# usb3.net
KiCad netlist of a schematic drawn in EAGLE
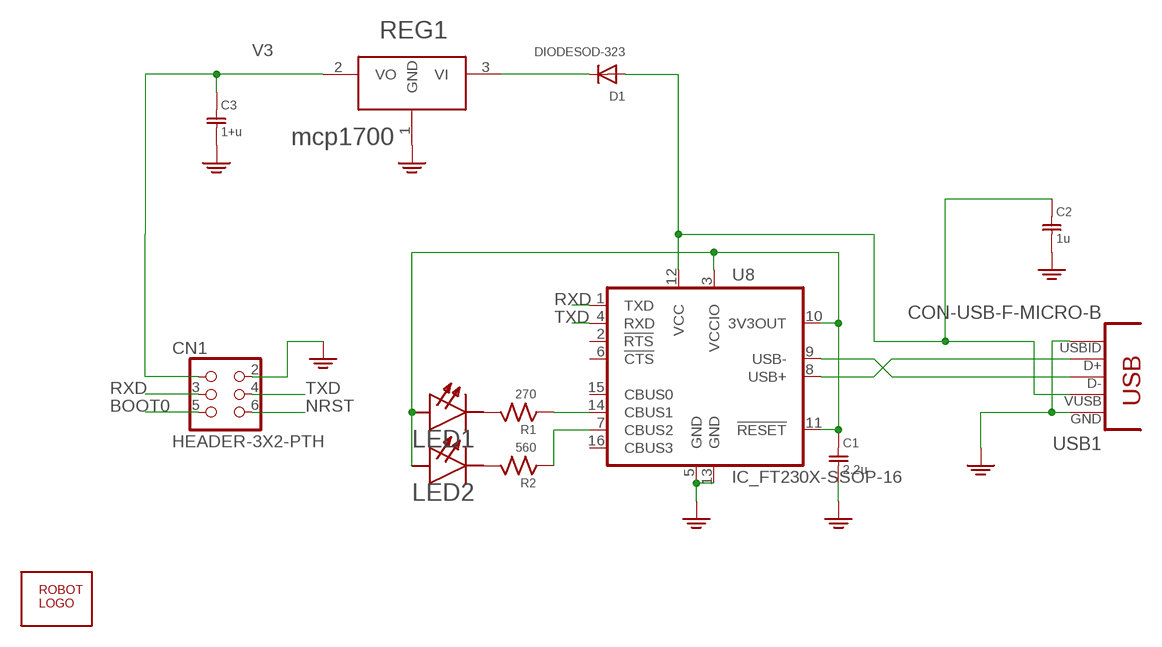
[diagram p0: schematic, sheet 1]

(export (version "E")
  (design (tool "Eeschema 10.0.6"))
  (components
    (comp (ref "C1")
      (value "2.2u")
      (footprint "eagle-import:SMD0603")
      (libsource (lib "eagle-import") (part "C0603"))
    )
    (comp (ref "C2")
      (value "1u")
      (footprint "eagle-import:SMD0603")
      (libsource (lib "eagle-import") (part "C0603"))
    )
    (comp (ref "C3")
      (value "1+u")
      (footprint "eagle-import:SMD0603")
      (libsource (lib "eagle-import") (part "C0603"))
    )
    (comp (ref "CN1")
      (value "HEADER-3X2-PTH")
      (footprint "eagle-import:HEADER-3X2-PTH")
      (libsource (lib "eagle-import") (part "HEADER-3X2-PTH"))
    )
    (comp (ref "D1")
      (value "DIODESOD-323")
      (footprint "eagle-import:SOD-323")
      (libsource (lib "eagle-import") (part "DIODESOD-323"))
    )
    (comp (ref "LED1")
      (value "GREEN")
      (footprint "eagle-import:SMD0603D")
      (libsource (lib "eagle-import") (part "LED"))
    )
    (comp (ref "LED2")
      (value "ORANGE")
      (footprint "eagle-import:SMD0603D")
      (libsource (lib "eagle-import") (part "LED"))
    )
    (comp (ref "R1")
      (value "270")
      (footprint "eagle-import:SMD0603")
      (libsource (lib "eagle-import") (part "R0603"))
    )
    (comp (ref "R2")
      (value "560")
      (footprint "eagle-import:SMD0603")
      (libsource (lib "eagle-import") (part "R0603"))
    )
    (comp (ref "REG1")
      (value "mcp1700")
      (footprint "eagle-import:SOT-23-3")
      (libsource (lib "eagle-import") (part "REGULATOR-SOT23-3"))
    )
    (comp (ref "U$1")
      (value "ROBOTMAN-LOGO")
      (footprint "eagle-import:ROBOTMAN-LOGO")
      (libsource (lib "eagle-import") (part "ROBOTMAN-LOGO"))
    )
    (comp (ref "U8")
      (value "IC_FT230X-SSOP-16")
      (footprint "eagle-import:SSOP-16-FTDI")
      (libsource (lib "eagle-import") (part "IC_FT230X-SSOP-16"))
    )
    (comp (ref "USB1")
      (value "CON-USB-F-MICRO-B")
      (footprint "eagle-import:CONN_USB_MICRO-B")
      (libsource (lib "eagle-import") (part "CON-USB-F-MICRO-B"))
    )
  )
  (nets
    (net (code "1") (name "/BOOT0") (class "Default")
      (node (ref "CN1") (pin "5") (pinfunction "P$5_5") (pintype "passive"))
    )
    (net (code "2") (name "/NRST") (class "Default")
      (node (ref "CN1") (pin "6") (pinfunction "P$6_6") (pintype "passive"))
    )
    (net (code "3") (name "/RXD") (class "Default")
      (node (ref "CN1") (pin "3") (pinfunction "P$3_3") (pintype "passive"))
      (node (ref "U8") (pin "1") (pinfunction "TXD_1") (pintype "output"))
    )
    (net (code "4") (name "/TXD") (class "Default")
      (node (ref "CN1") (pin "4") (pinfunction "P$4_4") (pintype "passive"))
      (node (ref "U8") (pin "4") (pinfunction "RXD_4") (pintype "input"))
    )
    (net (code "5") (name "/V3") (class "Default")
      (node (ref "C3") (pin "1") (pinfunction "P$1_1") (pintype "passive"))
      (node (ref "CN1") (pin "1") (pinfunction "P$1_1") (pintype "passive"))
      (node (ref "REG1") (pin "2") (pinfunction "VO_2") (pintype "bidirectional"))
    )
    (net (code "6") (name "Net-(C1-P$1)") (class "Default")
      (node (ref "C1") (pin "1") (pinfunction "P$1_1") (pintype "passive"))
      (node (ref "LED1") (pin "A") (pinfunction "A_A") (pintype "passive"))
      (node (ref "LED2") (pin "A") (pinfunction "A_A") (pintype "passive"))
      (node (ref "U8") (pin "10") (pinfunction "3V3OUT_10") (pintype "power_in"))
      (node (ref "U8") (pin "11") (pinfunction "~{RESET}_11") (pintype "bidirectional"))
      (node (ref "U8") (pin "3") (pinfunction "VCCIO_3") (pintype "power_in"))
    )
    (net (code "7") (name "Net-(C2-P$1)") (class "Default")
      (node (ref "C2") (pin "1") (pinfunction "P$1_1") (pintype "passive"))
      (node (ref "D1") (pin "A") (pinfunction "A_A") (pintype "passive"))
      (node (ref "U8") (pin "12") (pinfunction "VCC_12") (pintype "power_in"))
      (node (ref "USB1") (pin "P1") (pinfunction "VUSB_P1") (pintype "bidirectional"))
    )
    (net (code "8") (name "Net-(R1-P$1)") (class "Default")
      (node (ref "R1") (pin "1") (pinfunction "P$1_1") (pintype "passive"))
      (node (ref "U8") (pin "14") (pinfunction "CBUS1_14") (pintype "bidirectional"))
    )
    (net (code "9") (name "Net-(R1-P$2)") (class "Default")
      (node (ref "LED1") (pin "C") (pinfunction "C_C") (pintype "passive"))
      (node (ref "R1") (pin "2") (pinfunction "P$2_2") (pintype "passive"))
    )
    (net (code "10") (name "Net-(R2-P$1)") (class "Default")
      (node (ref "R2") (pin "1") (pinfunction "P$1_1") (pintype "passive"))
      (node (ref "U8") (pin "7") (pinfunction "CBUS2_7") (pintype "bidirectional"))
    )
    (net (code "11") (name "Net-(R2-P$2)") (class "Default")
      (node (ref "LED2") (pin "C") (pinfunction "C_C") (pintype "passive"))
      (node (ref "R2") (pin "2") (pinfunction "P$2_2") (pintype "passive"))
    )
    (net (code "12") (name "Net-(REG1-VI)") (class "Default")
      (node (ref "D1") (pin "C") (pinfunction "C_C") (pintype "passive"))
      (node (ref "REG1") (pin "3") (pinfunction "VI_3") (pintype "bidirectional"))
    )
    (net (code "13") (name "Net-(U8-USB+)") (class "Default")
      (node (ref "U8") (pin "8") (pinfunction "USB+_8") (pintype "output"))
      (node (ref "USB1") (pin "P3") (pinfunction "D+_P3") (pintype "bidirectional"))
    )
    (net (code "14") (name "Net-(U8-USB-)") (class "Default")
      (node (ref "U8") (pin "9") (pinfunction "USB-_9") (pintype "input"))
      (node (ref "USB1") (pin "P2") (pinfunction "D-_P2") (pintype "bidirectional"))
    )
    (net (code "15") (name "PWR-GND") (class "Default")
      (node (ref "C1") (pin "2") (pinfunction "P$2_2") (pintype "passive"))
      (node (ref "C2") (pin "2") (pinfunction "P$2_2") (pintype "passive"))
      (node (ref "C3") (pin "2") (pinfunction "P$2_2") (pintype "passive"))
      (node (ref "CN1") (pin "2") (pinfunction "P$2_2") (pintype "passive"))
      (node (ref "REG1") (pin "1") (pinfunction "GND_1") (pintype "bidirectional"))
      (node (ref "U8") (pin "13") (pinfunction "GND_13") (pintype "power_in"))
      (node (ref "U8") (pin "5") (pinfunction "GND_5") (pintype "power_in"))
      (node (ref "USB1") (pin "P4") (pinfunction "USBID_P4") (pintype "bidirectional"))
      (node (ref "USB1") (pin "P5") (pinfunction "GND_P5") (pintype "bidirectional"))
    )
    (net (code "16") (name "unconnected-(U8-CBUS0-Pad15)") (class "Default")
      (node (ref "U8") (pin "15") (pinfunction "CBUS0_15") (pintype "bidirectional"))
    )
    (net (code "17") (name "unconnected-(U8-CBUS3-Pad16)") (class "Default")
      (node (ref "U8") (pin "16") (pinfunction "CBUS3_16") (pintype "bidirectional"))
    )
    (net (code "18") (name "unconnected-(U8-~{CTS}-Pad6)") (class "Default")
      (node (ref "U8") (pin "6") (pinfunction "~{CTS}_6") (pintype "bidirectional"))
    )
    (net (code "19") (name "unconnected-(U8-~{RTS}-Pad2)") (class "Default")
      (node (ref "U8") (pin "2") (pinfunction "~{RTS}_2") (pintype "bidirectional"))
    )
  )
)
